# Power_switch_robot_kecil_-_Copy.net
KiCad netlist of a schematic drawn in EAGLE
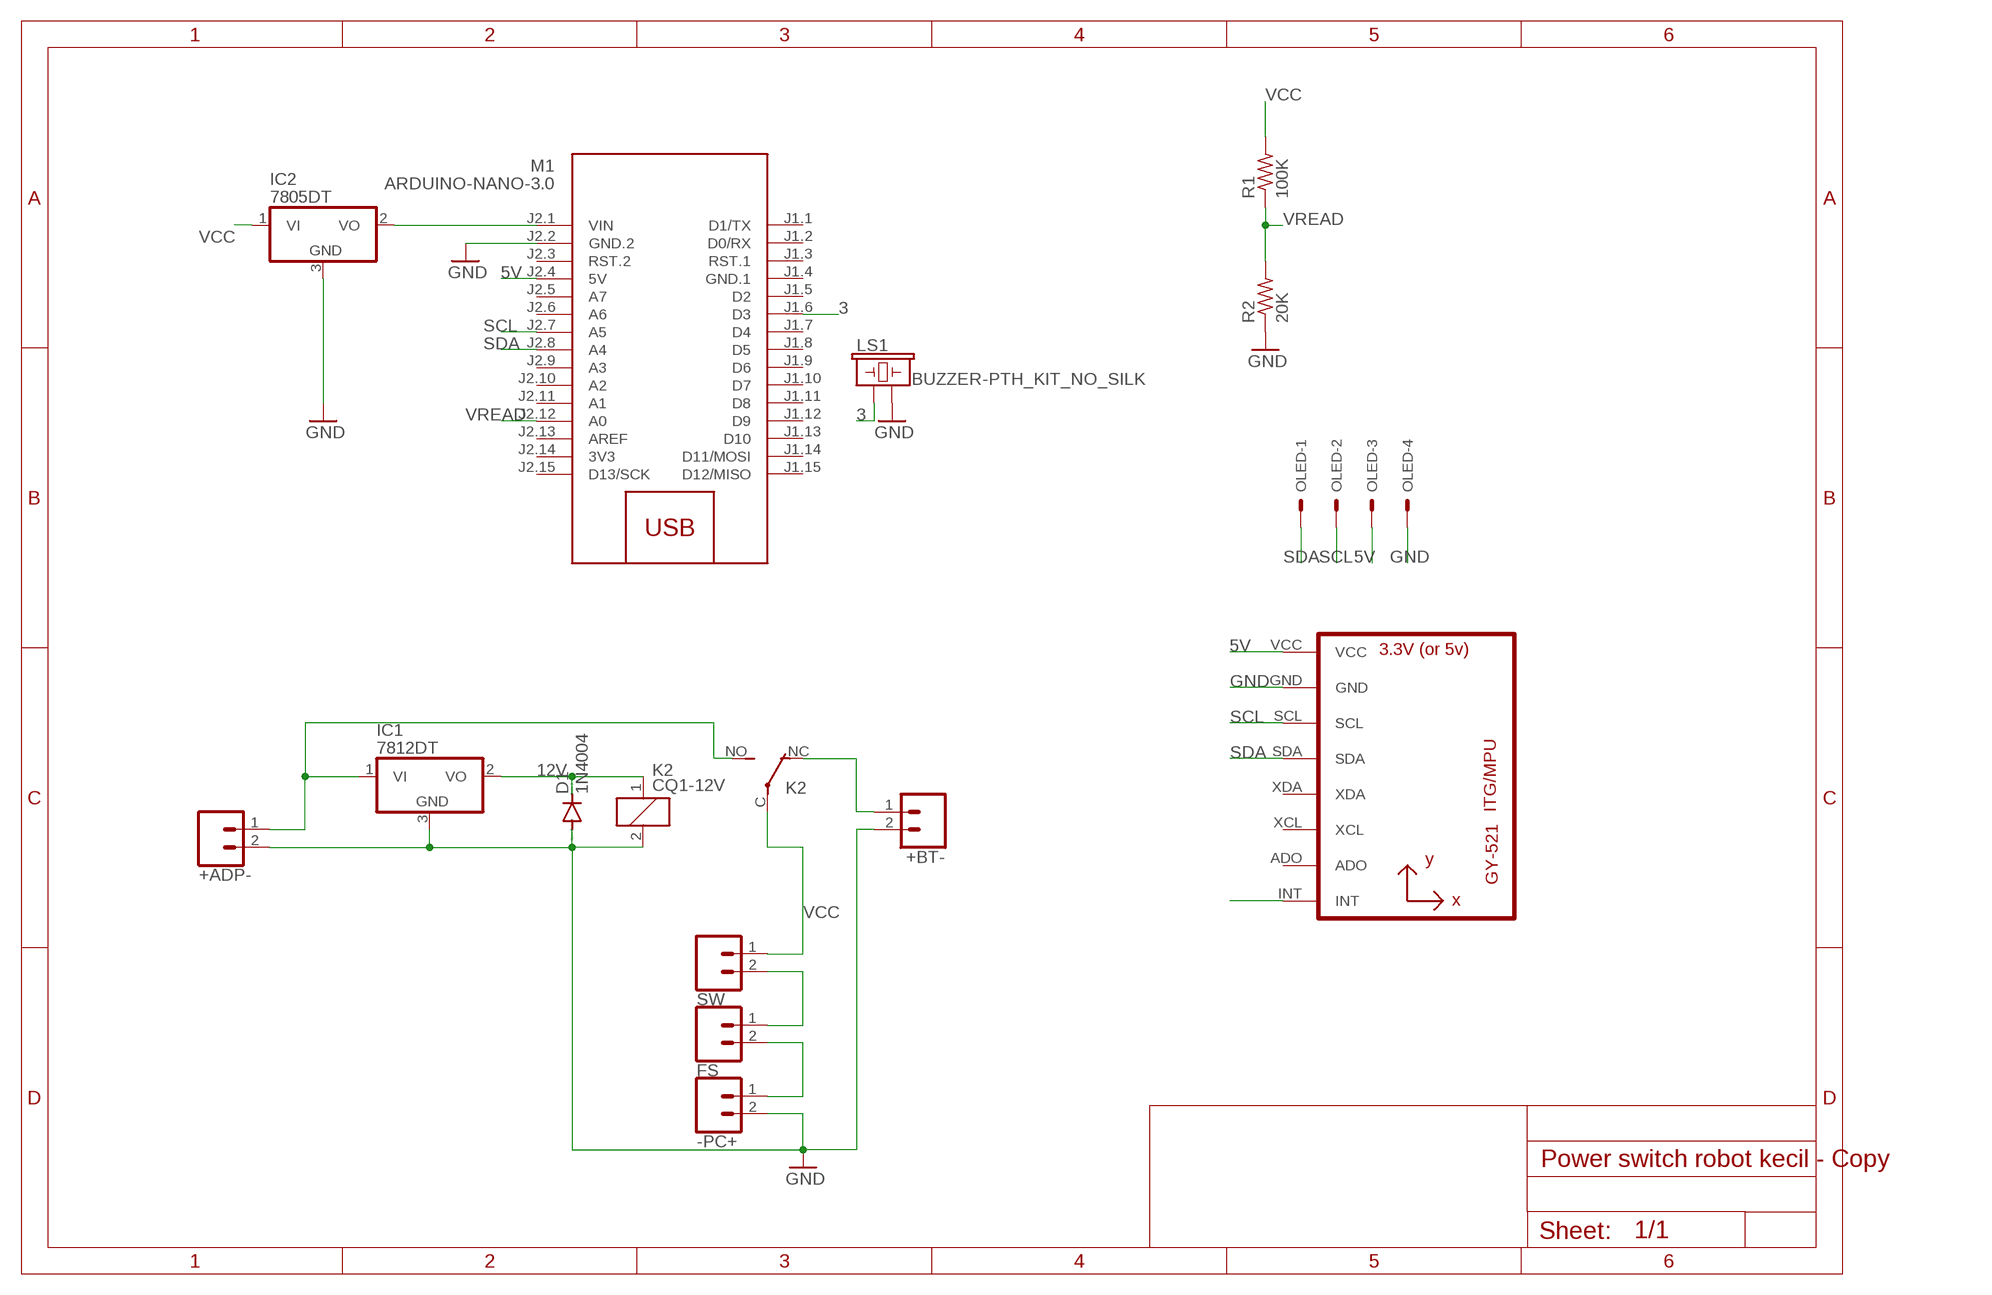
[diagram p0: schematic, sheet 1]

(export (version "E")
  (design (tool "Eeschema 10.0.6"))
  (components
    (comp (ref "+ADP-")
      (value "CONN_02LOCK_LONGPADS")
      (footprint "eagle-import:1X02_LOCK_LONGPADS")
      (libsource (lib "eagle-import") (part "CONN_02LOCK_LONGPADS"))
    )
    (comp (ref "+BT-")
      (value "CONN_02LOCK_LONGPADS")
      (footprint "eagle-import:1X02_LOCK_LONGPADS")
      (libsource (lib "eagle-import") (part "CONN_02LOCK_LONGPADS"))
    )
    (comp (ref "-PC+")
      (value "CONN_02LOCK_LONGPADS")
      (footprint "eagle-import:1X02_LOCK_LONGPADS")
      (libsource (lib "eagle-import") (part "CONN_02LOCK_LONGPADS"))
    )
    (comp (ref "D1")
      (value "1N4004")
      (footprint "eagle-import:DO41-10")
      (libsource (lib "eagle-import") (part "1N4004"))
    )
    (comp (ref "FS")
      (value "CONN_02LOCK_LONGPADS")
      (footprint "eagle-import:1X02_LOCK_LONGPADS")
      (libsource (lib "eagle-import") (part "CONN_02LOCK_LONGPADS"))
    )
    (comp (ref "IC1")
      (value "7812DT")
      (footprint "eagle-import:TO252")
      (libsource (lib "eagle-import") (part "78DT12"))
    )
    (comp (ref "IC2")
      (value "7805DT")
      (footprint "eagle-import:TO252")
      (libsource (lib "eagle-import") (part "78DT05"))
    )
    (comp (ref "K2")
      (value "CQ1-12V")
      (footprint "eagle-import:CQ1")
      (libsource (lib "eagle-import") (part "CQ1-12V"))
    )
    (comp (ref "LS1")
      (value "BUZZER-PTH_KIT_NO_SILK")
      (footprint "eagle-import:BUZZER-12MM-NS-KIT")
      (libsource (lib "eagle-import") (part "BUZZER-PTH_KIT_NO_SILK"))
    )
    (comp (ref "M1")
      (value "ARDUINO-NANO-3.0")
      (footprint "eagle-import:ARDUINO-NANO-3.0")
      (libsource (lib "eagle-import") (part "ARDUINO-NANO-3.0"))
    )
    (comp (ref "OLED")
      (value "22-27-2041-04")
      (footprint "eagle-import:6410-04")
      (fields (field (name "MF") "MOLEX"))
      (libsource (lib "eagle-import") (part "22-?-0427-2041"))
    )
    (comp (ref "R1")
      (value "100K")
      (footprint "eagle-import:0207_10")
      (libsource (lib "eagle-import") (part "R-US_0207/10"))
    )
    (comp (ref "R2")
      (value "20K")
      (footprint "eagle-import:0207_10")
      (libsource (lib "eagle-import") (part "R-US_0207/10"))
    )
    (comp (ref "SW")
      (value "CONN_02LOCK_LONGPADS")
      (footprint "eagle-import:1X02_LOCK_LONGPADS")
      (libsource (lib "eagle-import") (part "CONN_02LOCK_LONGPADS"))
    )
    (comp (ref "U1")
      (value "GY-521MPU6050")
      (footprint "eagle-import:GY-521")
      (libsource (lib "eagle-import") (part "GY-521MPU6050"))
    )
  )
  (nets
    (net (code "1") (name "/3") (class "Default")
      (node (ref "LS1") (pin "+") (pinfunction "1_+") (pintype "passive"))
      (node (ref "M1") (pin "J1.6") (pinfunction "D3_J1.6") (pintype "bidirectional"))
    )
    (net (code "2") (name "/3V3") (class "Default")
      (node (ref "M1") (pin "J2.14") (pinfunction "3V3_J2.14") (pintype "power_in"))
    )
    (net (code "3") (name "/5V") (class "Default")
      (node (ref "M1") (pin "J2.4") (pinfunction "5V_J2.4") (pintype "power_in"))
      (node (ref "OLED") (pin "3") (pinfunction "S_3") (pintype "passive"))
      (node (ref "U1") (pin "VCC") (pinfunction "VCC_VCC") (pintype "bidirectional"))
    )
    (net (code "4") (name "/12V") (class "Default")
      (node (ref "D1") (pin "C") (pinfunction "C_C") (pintype "passive"))
      (node (ref "IC1") (pin "2") (pinfunction "VO_2") (pintype "passive"))
      (node (ref "K2") (pin "1") (pinfunction "1_1") (pintype "passive"))
    )
    (net (code "5") (name "/GND.1") (class "Default")
      (node (ref "M1") (pin "J1.4") (pinfunction "GND.1_J1.4") (pintype "power_in"))
    )
    (net (code "6") (name "/SCL") (class "Default")
      (node (ref "M1") (pin "J2.7") (pinfunction "A5_J2.7") (pintype "bidirectional"))
      (node (ref "OLED") (pin "2") (pinfunction "S_2") (pintype "passive"))
      (node (ref "U1") (pin "SCL") (pinfunction "SCL_SCL") (pintype "bidirectional"))
    )
    (net (code "7") (name "/SDA") (class "Default")
      (node (ref "M1") (pin "J2.8") (pinfunction "A4_J2.8") (pintype "bidirectional"))
      (node (ref "OLED") (pin "1") (pinfunction "S_1") (pintype "passive"))
      (node (ref "U1") (pin "SDA") (pinfunction "SDA_SDA") (pintype "bidirectional"))
    )
    (net (code "8") (name "/VCC") (class "Default")
      (node (ref "IC2") (pin "1") (pinfunction "VI_1") (pintype "input"))
      (node (ref "K2") (pin "C") (pinfunction "P_C") (pintype "passive"))
      (node (ref "R1") (pin "2") (pinfunction "2_2") (pintype "passive"))
      (node (ref "SW") (pin "1") (pinfunction "1_1") (pintype "passive"))
    )
    (net (code "9") (name "/VREAD") (class "Default")
      (node (ref "M1") (pin "J2.12") (pinfunction "A0_J2.12") (pintype "bidirectional"))
      (node (ref "R1") (pin "1") (pinfunction "1_1") (pintype "passive"))
      (node (ref "R2") (pin "2") (pinfunction "2_2") (pintype "passive"))
    )
    (net (code "10") (name "GND") (class "Default")
      (node (ref "+ADP-") (pin "2") (pinfunction "2_2") (pintype "passive"))
      (node (ref "+BT-") (pin "2") (pinfunction "2_2") (pintype "passive"))
      (node (ref "-PC+") (pin "2") (pinfunction "2_2") (pintype "passive"))
      (node (ref "D1") (pin "A") (pinfunction "A_A") (pintype "passive"))
      (node (ref "IC1") (pin "3") (pinfunction "GND_3") (pintype "passive"))
      (node (ref "IC2") (pin "3") (pinfunction "GND_3") (pintype "passive"))
      (node (ref "K2") (pin "2") (pinfunction "2_2") (pintype "passive"))
      (node (ref "LS1") (pin "-") (pinfunction "2_-") (pintype "passive"))
      (node (ref "M1") (pin "J2.2") (pinfunction "GND.2_J2.2") (pintype "power_in"))
      (node (ref "OLED") (pin "4") (pinfunction "S_4") (pintype "passive"))
      (node (ref "R2") (pin "1") (pinfunction "1_1") (pintype "passive"))
      (node (ref "U1") (pin "GND") (pinfunction "GND_GND") (pintype "bidirectional"))
    )
    (net (code "11") (name "Net-(-PC+-Pad1)") (class "Default")
      (node (ref "-PC+") (pin "1") (pinfunction "1_1") (pintype "passive"))
      (node (ref "FS") (pin "2") (pinfunction "2_2") (pintype "passive"))
    )
    (net (code "12") (name "Net-(FS-Pad1)") (class "Default")
      (node (ref "FS") (pin "1") (pinfunction "1_1") (pintype "passive"))
      (node (ref "SW") (pin "2") (pinfunction "2_2") (pintype "passive"))
    )
    (net (code "13") (name "Net-(IC1-VI)") (class "Default")
      (node (ref "+ADP-") (pin "1") (pinfunction "1_1") (pintype "passive"))
      (node (ref "IC1") (pin "1") (pinfunction "VI_1") (pintype "input"))
      (node (ref "K2") (pin "NO") (pinfunction "S_NO") (pintype "passive"))
    )
    (net (code "14") (name "Net-(IC2-VO)") (class "Default")
      (node (ref "IC2") (pin "2") (pinfunction "VO_2") (pintype "passive"))
      (node (ref "M1") (pin "J2.1") (pinfunction "VIN_J2.1") (pintype "power_in"))
    )
    (net (code "15") (name "Net-(K2B-O)") (class "Default")
      (node (ref "+BT-") (pin "1") (pinfunction "1_1") (pintype "passive"))
      (node (ref "K2") (pin "NC") (pinfunction "O_NC") (pintype "passive"))
    )
    (net (code "16") (name "unconnected-(M1-A1-PadJ2.11)") (class "Default")
      (node (ref "M1") (pin "J2.11") (pinfunction "A1_J2.11") (pintype "bidirectional"))
    )
    (net (code "17") (name "unconnected-(M1-A2-PadJ2.10)") (class "Default")
      (node (ref "M1") (pin "J2.10") (pinfunction "A2_J2.10") (pintype "bidirectional"))
    )
    (net (code "18") (name "unconnected-(M1-A3-PadJ2.9)") (class "Default")
      (node (ref "M1") (pin "J2.9") (pinfunction "A3_J2.9") (pintype "bidirectional"))
    )
    (net (code "19") (name "unconnected-(M1-A6-PadJ2.6)") (class "Default")
      (node (ref "M1") (pin "J2.6") (pinfunction "A6_J2.6") (pintype "bidirectional"))
    )
    (net (code "20") (name "unconnected-(M1-A7-PadJ2.5)") (class "Default")
      (node (ref "M1") (pin "J2.5") (pinfunction "A7_J2.5") (pintype "bidirectional"))
    )
    (net (code "21") (name "unconnected-(M1-AREF-PadJ2.13)") (class "Default")
      (node (ref "M1") (pin "J2.13") (pinfunction "AREF_J2.13") (pintype "bidirectional"))
    )
    (net (code "22") (name "unconnected-(M1-D0{slash}RX-PadJ1.2)") (class "Default")
      (node (ref "M1") (pin "J1.2") (pinfunction "D0/RX_J1.2") (pintype "bidirectional"))
    )
    (net (code "23") (name "unconnected-(M1-D1{slash}TX-PadJ1.1)") (class "Default")
      (node (ref "M1") (pin "J1.1") (pinfunction "D1/TX_J1.1") (pintype "bidirectional"))
    )
    (net (code "24") (name "unconnected-(M1-D2-PadJ1.5)") (class "Default")
      (node (ref "M1") (pin "J1.5") (pinfunction "D2_J1.5") (pintype "bidirectional"))
    )
    (net (code "25") (name "unconnected-(M1-D4-PadJ1.7)") (class "Default")
      (node (ref "M1") (pin "J1.7") (pinfunction "D4_J1.7") (pintype "bidirectional"))
    )
    (net (code "26") (name "unconnected-(M1-D5-PadJ1.8)") (class "Default")
      (node (ref "M1") (pin "J1.8") (pinfunction "D5_J1.8") (pintype "bidirectional"))
    )
    (net (code "27") (name "unconnected-(M1-D6-PadJ1.9)") (class "Default")
      (node (ref "M1") (pin "J1.9") (pinfunction "D6_J1.9") (pintype "bidirectional"))
    )
    (net (code "28") (name "unconnected-(M1-D7-PadJ1.10)") (class "Default")
      (node (ref "M1") (pin "J1.10") (pinfunction "D7_J1.10") (pintype "bidirectional"))
    )
    (net (code "29") (name "unconnected-(M1-D8-PadJ1.11)") (class "Default")
      (node (ref "M1") (pin "J1.11") (pinfunction "D8_J1.11") (pintype "bidirectional"))
    )
    (net (code "30") (name "unconnected-(M1-D9-PadJ1.12)") (class "Default")
      (node (ref "M1") (pin "J1.12") (pinfunction "D9_J1.12") (pintype "bidirectional"))
    )
    (net (code "31") (name "unconnected-(M1-D10-PadJ1.13)") (class "Default")
      (node (ref "M1") (pin "J1.13") (pinfunction "D10_J1.13") (pintype "bidirectional"))
    )
    (net (code "32") (name "unconnected-(M1-D11{slash}MOSI-PadJ1.14)") (class "Default")
      (node (ref "M1") (pin "J1.14") (pinfunction "D11/MOSI_J1.14") (pintype "bidirectional"))
    )
    (net (code "33") (name "unconnected-(M1-D12{slash}MISO-PadJ1.15)") (class "Default")
      (node (ref "M1") (pin "J1.15") (pinfunction "D12/MISO_J1.15") (pintype "bidirectional"))
    )
    (net (code "34") (name "unconnected-(M1-D13{slash}SCK-PadJ2.15)") (class "Default")
      (node (ref "M1") (pin "J2.15") (pinfunction "D13/SCK_J2.15") (pintype "bidirectional"))
    )
    (net (code "35") (name "unconnected-(M1-RST.1-PadJ1.3)") (class "Default")
      (node (ref "M1") (pin "J1.3") (pinfunction "RST.1_J1.3") (pintype "bidirectional"))
    )
    (net (code "36") (name "unconnected-(M1-RST.2-PadJ2.3)") (class "Default")
      (node (ref "M1") (pin "J2.3") (pinfunction "RST.2_J2.3") (pintype "bidirectional"))
    )
    (net (code "37") (name "unconnected-(U1-PadADO)") (class "Default")
      (node (ref "U1") (pin "ADO") (pinfunction "ADO_ADO") (pintype "bidirectional"))
    )
    (net (code "38") (name "unconnected-(U1-PadINT)") (class "Default")
      (node (ref "U1") (pin "INT") (pinfunction "INT_INT") (pintype "bidirectional"))
    )
    (net (code "39") (name "unconnected-(U1-PadXCL)") (class "Default")
      (node (ref "U1") (pin "XCL") (pinfunction "XCL_XCL") (pintype "bidirectional"))
    )
    (net (code "40") (name "unconnected-(U1-PadXDA)") (class "Default")
      (node (ref "U1") (pin "XDA") (pinfunction "XDA_XDA") (pintype "bidirectional"))
    )
  )
)
